# 12V_Power.net
KiCad netlist of a schematic drawn in Altium Designer
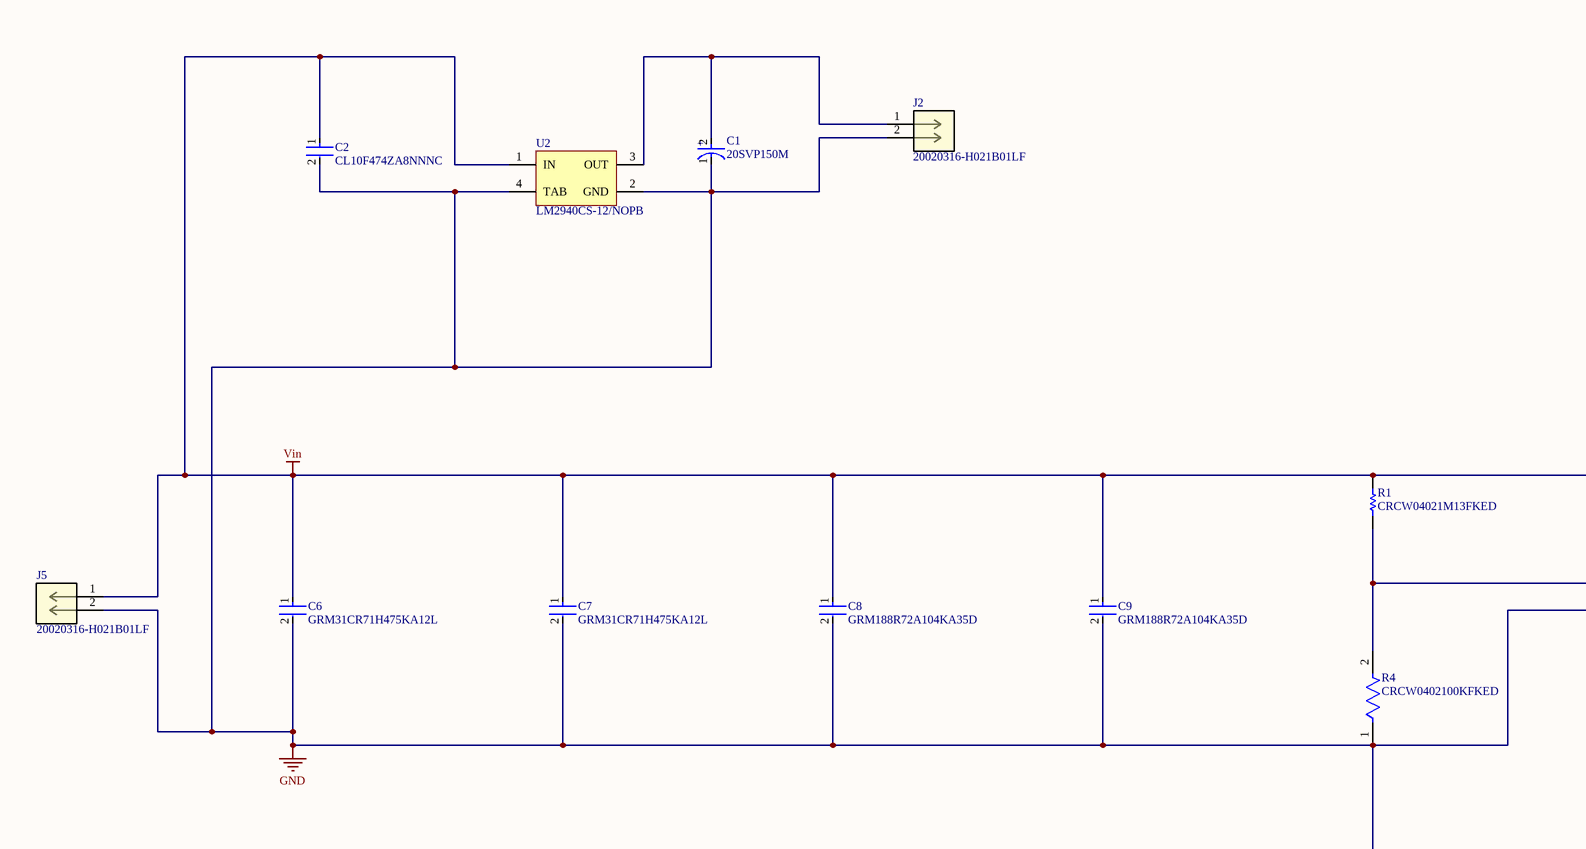
[diagram p0: 12V Power.SchDoc, left]
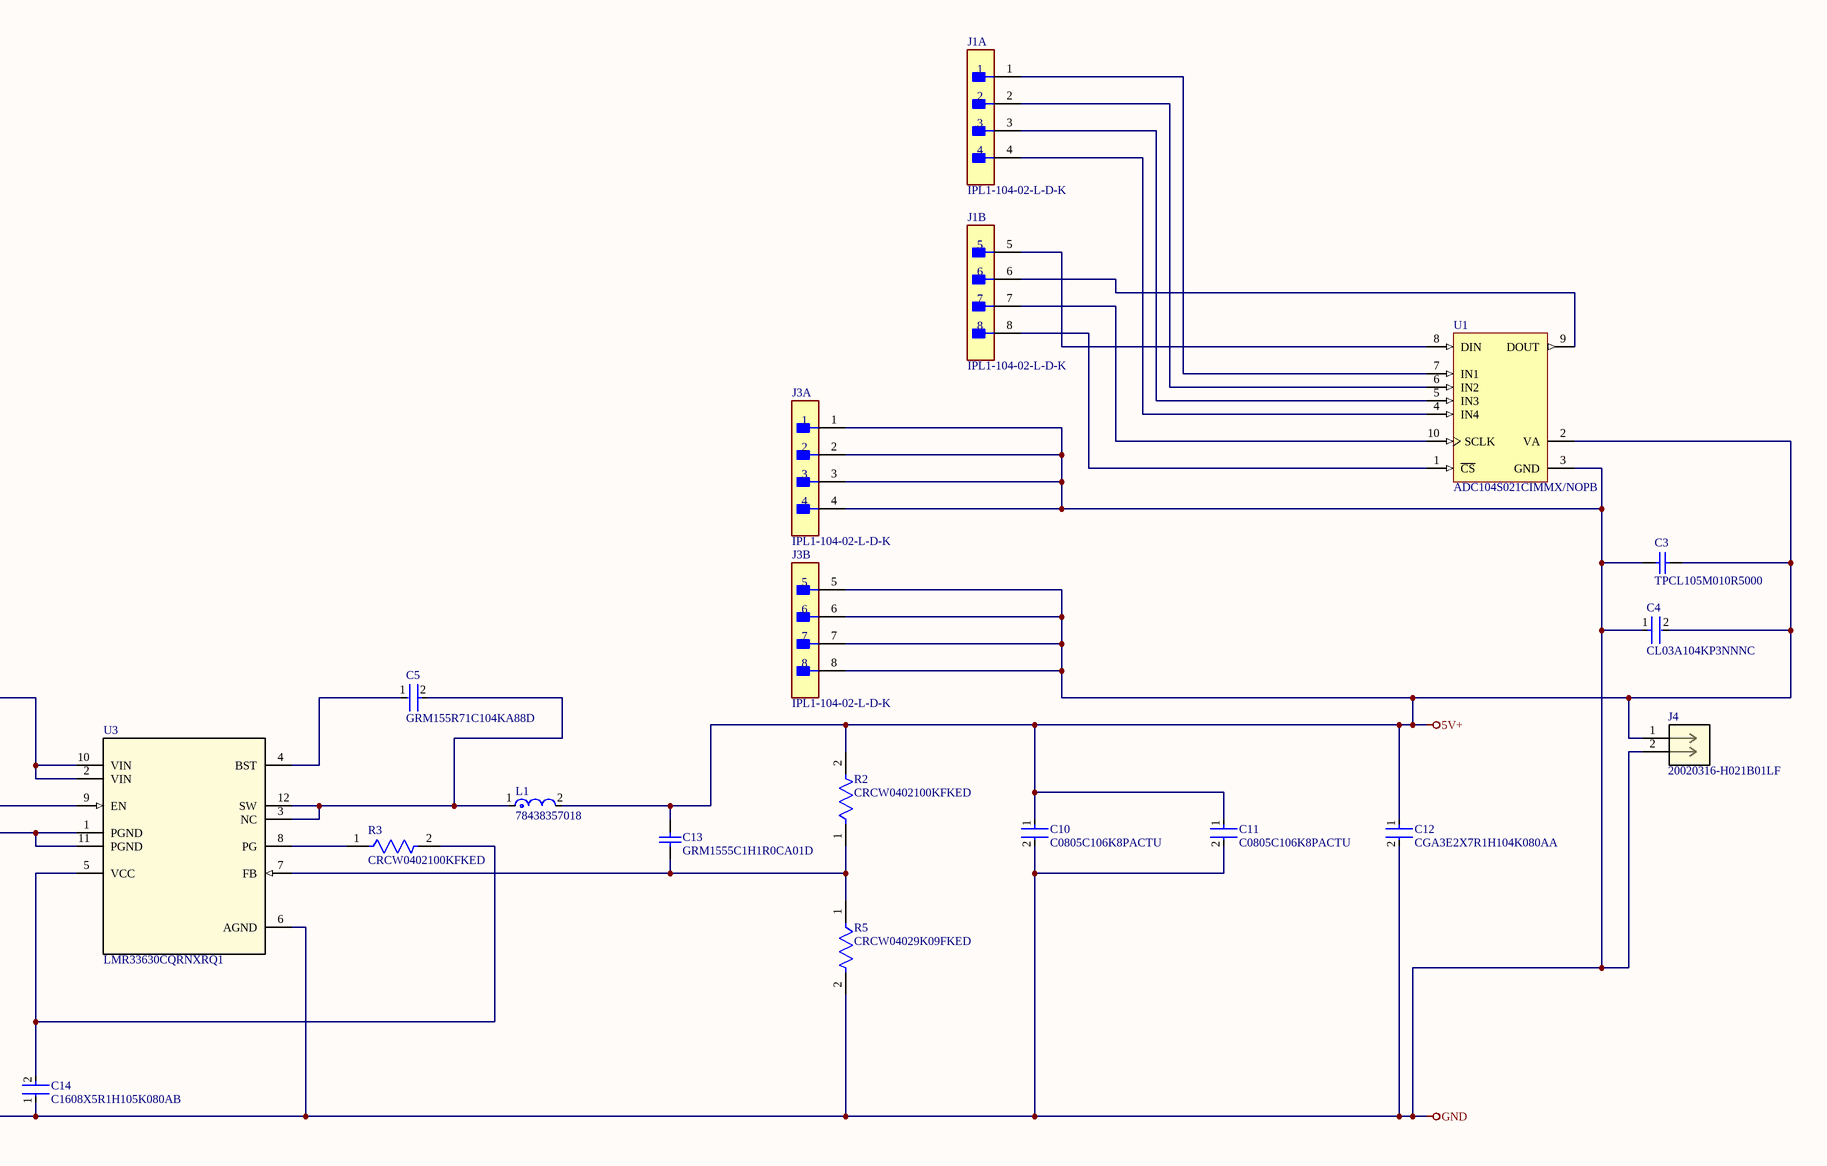
[diagram p1: 12V Power.SchDoc, right]

(export (version "E")
  (design (tool "Eeschema 10.0.6"))
  (components
    (comp (ref "C1")
      (value "20SVP150M")
      (footprint "FP-OS-CON-SMT-F12-MFG")
      (description "Conductive Polymer Aluminum Solid Capacitors (OS-CON) 150uF ±20% 20V RADIAL SMT 10x12.6mm")
      (fields (field (name "TOLERANCE") "20%") (field (name "VOLTAGE") "20V"))
      (libsource (lib "Altium Content Vault") (part "a7907c86e72a156c28511143de7831b"))
    )
    (comp (ref "C2")
      (value "CL10F474ZA8NNNC")
      (footprint "FP-CL10-IPC_C")
      (description "Cap Ceramic 470nF 25V Y5V -20/+80% Pad SMD 0603 +85°C T/R")
      (fields (field (name "TOLERANCE") "80%"))
      (libsource (lib "Altium Content Vault") (part "b4654b650e69147ec39a6b967a45e02"))
    )
    (comp (ref "C3")
      (value "TPCL105M010R5000")
      (footprint "CAPC1609X100X15LL20")
      (fields (field (name "MANUFACTURER") "AVX Interconnect / Elco"))
      (libsource (lib "Altium Content Vault") (part "CAP"))
    )
    (comp (ref "C4")
      (value "CL03A104KP3NNNC")
      (footprint "FP-CL03-IPC_C")
      (description "Cap Ceramic 100nF 10V X5R ±10% Pad SMD 0201 +85°C T/R")
      (fields (field (name "TOLERANCE") "10%"))
      (libsource (lib "Altium Content Vault") (part "b4654b650e69147ec39a6b967a45e02"))
    )
    (comp (ref "C5")
      (value "GRM155R71C104KA88D")
      (footprint "FP-GRM15-MFG")
      (description "CAP CER 0.1UF 16V X7R 0402")
      (fields
        (field (name "TOLERANCE") "10%")
        (field (name "OCTOPART") "https://octopart.com/grm155r71c104ka88d-murata-196880")
      )
      (libsource (lib "Altium Content Vault") (part "236180d848d6139a670b325ea6854c9"))
    )
    (comp (ref "C6")
      (value "GRM31CR71H475KA12L")
      (footprint "FP-GRM31C-0_2-e0_3_0_8-IPC_C")
      (description "Chip Multilayer Ceramic Capacitors for General Purpose, 1206, 4.7uF, X7R, 15%, 10%, 50V")
      (fields (field (name "VOLTAGE") "50V") (field (name "TOLERANCE") "10%"))
      (libsource (lib "Altium Content Vault") (part "02cd4be3c70576c341d710602a673aa"))
    )
    (comp (ref "C7")
      (value "GRM31CR71H475KA12L")
      (footprint "FP-GRM31C-0_2-e0_3_0_8-IPC_C")
      (description "Chip Multilayer Ceramic Capacitors for General Purpose, 1206, 4.7uF, X7R, 15%, 10%, 50V")
      (fields (field (name "VOLTAGE") "50V") (field (name "TOLERANCE") "10%"))
      (libsource (lib "Altium Content Vault") (part "02cd4be3c70576c341d710602a673aa"))
    )
    (comp (ref "C8")
      (value "GRM188R72A104KA35D")
      (footprint "FP-GRM188-0_1-e0_2_0_5-IPC_B")
      (description "Chip Multilayer Ceramic Capacitors for General Purpose, 0603, 0.10uF, X7R, 15%, 10%, 100V")
      (fields (field (name "VOLTAGE") "100V") (field (name "TOLERANCE") "10%"))
      (libsource (lib "Altium Content Vault") (part "11868f565c42a9108669ba33697ecf6"))
    )
    (comp (ref "C9")
      (value "GRM188R72A104KA35D")
      (footprint "FP-GRM188-0_1-e0_2_0_5-IPC_B")
      (description "Chip Multilayer Ceramic Capacitors for General Purpose, 0603, 0.10uF, X7R, 15%, 10%, 100V")
      (fields (field (name "VOLTAGE") "100V") (field (name "TOLERANCE") "10%"))
      (libsource (lib "Altium Content Vault") (part "11868f565c42a9108669ba33697ecf6"))
    )
    (comp (ref "C10")
      (value "C0805C106K8PACTU")
      (footprint "FP-C0805C-DG-MFG")
      (description "CAP CER 10UF 10V X5R 0805")
      (fields (field (name "TOLERANCE") "10%") (field (name "MANUFACTURER") "Kemet"))
      (libsource (lib "Altium Content Vault") (part "11868f565c42a9108669ba33697ecf6"))
    )
    (comp (ref "C11")
      (value "C0805C106K8PACTU")
      (footprint "FP-C0805C-DG-MFG")
      (description "CAP CER 10UF 10V X5R 0805")
      (fields (field (name "TOLERANCE") "10%") (field (name "MANUFACTURER") "Kemet"))
      (libsource (lib "Altium Content Vault") (part "11868f565c42a9108669ba33697ecf6"))
    )
    (comp (ref "C12")
      (value "CGA3E2X7R1H104K080AA")
      (footprint "FP-CGA3E-0_3-0_1-IPC_A")
      (description "Cap Ceramic 100nF 50V X7R 10% Pad SMD 0603 +125°C Automotive T/R")
      (fields (field (name "TOLERANCE") "10%") (field (name "VOLTAGE") "50V"))
      (libsource (lib "Altium Content Vault") (part "b4654b650e69147ec39a6b967a45e02"))
    )
    (comp (ref "C13")
      (value "GRM1555C1H1R0CA01D")
      (footprint "CAPC1005X55X25NL05T10")
      (fields (field (name "MANUFACTURER") "Murata"))
      (libsource (lib "Altium Content Vault") (part "CAP"))
    )
    (comp (ref "C14")
      (value "C1608X5R1H105K080AB")
      (footprint "FP-C1608-080-0_1-IPC_B")
      (description "Multilayer Ceramic Capacitors 1μF ±10% 50V X5R SMD 0603")
      (fields (field (name "VOLTAGE") "50V") (field (name "TOLERANCE") "10%"))
      (libsource (lib "Altium Content Vault") (part "236180d848d6139a670b325ea6854c9"))
    )
    (comp (ref "J1")
      (value "IPL1-104-02-L-D-K")
      (footprint "FP-IPL1-104-02-L-D-K-0")
      (description "4 Position 2 Row .100\" (2.54 mm) pitch connector")
      (libsource (lib "Altium Content Vault") (part "eac520707025fdf6420609226a638dc"))
    )
    (comp (ref "J2")
      (value "20020316-H021B01LF")
      (footprint "CONN_20020316-H021B01LF_AMP")
      (description "No Description Available")
      (fields (field (name "COPYRIGHT") "Copyright (C) 2022 Ultra Librarian. All rights reserved."))
      (libsource (lib "12V Power lib") (part "20020316-H021B01LF"))
    )
    (comp (ref "J3")
      (value "IPL1-104-02-L-D-K")
      (footprint "FP-IPL1-104-02-L-D-K-0")
      (description "4 Position 2 Row .100\" (2.54 mm) pitch connector")
      (libsource (lib "Altium Content Vault") (part "eac520707025fdf6420609226a638dc"))
    )
    (comp (ref "J4")
      (value "20020316-H021B01LF")
      (footprint "CONN_20020316-H021B01LF_AMP")
      (description "No Description Available")
      (fields (field (name "COPYRIGHT") "Copyright (C) 2022 Ultra Librarian. All rights reserved."))
      (libsource (lib "12V Power lib") (part "20020316-H021B01LF"))
    )
    (comp (ref "J5")
      (value "20020316-H021B01LF")
      (footprint "CONN_20020316-H021B01LF_AMP")
      (description "No Description Available")
      (fields (field (name "COPYRIGHT") "Copyright (C) 2022 Ultra Librarian. All rights reserved."))
      (libsource (lib "") (part "20020316-H021B01LF_1"))
    )
    (comp (ref "L1")
      (value "78438357018")
      (footprint "FP-78438357018-MFG")
      (description "FIXED IND 1.8UH 5.8A 21MOHM SMD")
      (fields (field (name "TOLERANCE") "20%"))
      (libsource (lib "Altium Content Vault") (part "4cc4b267dca4c8e51f7102f422741d8"))
    )
    (comp (ref "R1")
      (value "CRCW04021M13FKED")
      (footprint "RESC1005X40X25ML05T05")
      (fields (field (name "MANUFACTURER") "Vishay Dale"))
      (libsource (lib "Altium Content Vault") (part "RES"))
    )
    (comp (ref "R2")
      (value "CRCW0402100KFKED")
      (footprint "FP-CRCW0402-e3-IPC_C")
      (description "RES Thick Film, 100kΩ, 1%, 0.063W, 100ppm/°C, 0402")
      (fields (field (name "TOLERANCE") "1%"))
      (libsource (lib "Altium Content Vault") (part "1029c3af85768c4190bb7ad29bc67b5"))
    )
    (comp (ref "R3")
      (value "CRCW0402100KFKED")
      (footprint "FP-CRCW0402-e3-IPC_C")
      (description "RES Thick Film, 100kΩ, 1%, 0.063W, 100ppm/°C, 0402")
      (fields (field (name "TOLERANCE") "1%"))
      (libsource (lib "Altium Content Vault") (part "1029c3af85768c4190bb7ad29bc67b5"))
    )
    (comp (ref "R4")
      (value "CRCW0402100KFKED")
      (footprint "FP-CRCW0402-e3-IPC_C")
      (description "RES Thick Film, 100kΩ, 1%, 0.063W, 100ppm/°C, 0402")
      (fields (field (name "TOLERANCE") "1%"))
      (libsource (lib "Altium Content Vault") (part "1029c3af85768c4190bb7ad29bc67b5"))
    )
    (comp (ref "R5")
      (value "CRCW04029K09FKED")
      (footprint "FP-CRCW0402-e3-IPC_A")
      (description "RES Thick Film, 9.09kΩ, 1%, 0.063W, 100ppm/°C, 0402")
      (fields (field (name "TOLERANCE") "1%"))
      (libsource (lib "Altium Content Vault") (part "1029c3af85768c4190bb7ad29bc67b5"))
    )
    (comp (ref "U1")
      (value "ADC104S021CIMMX/NOPB")
      (footprint "MUB10A_N")
      (description "4 Channel, 50 kSPS to 200 kSPS, 10-Bit A/D Converter, 10-pin Mini SOIC, Pb-Free")
      (fields (field (name "MANUFACTURER") "National Semiconductor"))
      (libsource (lib "Altium Content Vault") (part "CON-ADC-ADC104S101CIMM"))
    )
    (comp (ref "U2")
      (value "LM2940CS-12/NOPB")
      (footprint "KTT0003B_N")
      (description "1A Low Dropout Regulator, 3-pin TO-263, Pb-Free")
      (fields (field (name "MANUFACTURER") "Texas Instruments"))
      (libsource (lib "Altium Content Vault") (part "PM-REG-LM2940-TO4"))
    )
    (comp (ref "U3")
      (value "LMR33630CQRNXRQ1")
      (footprint "RNX0012B")
      (description "No Description Available")
      (fields (field (name "COPYRIGHT") "Copyright (C) 2022 Ultra Librarian. All rights reserved."))
      (libsource (lib "12V Power lib") (part "LMR33630CQRNXRQ1_1"))
    )
  )
  (nets
    (net (code "1") (name "5V+") (class "Default")
      (node (ref "C10") (pin "1") (pinfunction "1_1") (pintype "passive"))
      (node (ref "C11") (pin "1") (pinfunction "1_1") (pintype "passive"))
      (node (ref "C12") (pin "1") (pinfunction "1_1") (pintype "passive"))
      (node (ref "C13") (pin "2") (pinfunction "2_2") (pintype "passive"))
      (node (ref "C3") (pin "1") (pinfunction "1_1") (pintype "passive"))
      (node (ref "C4") (pin "2") (pinfunction "2_2") (pintype "passive"))
      (node (ref "J3") (pin "5") (pinfunction "5_5") (pintype "passive"))
      (node (ref "J3") (pin "6") (pinfunction "6_6") (pintype "passive"))
      (node (ref "J3") (pin "7") (pinfunction "7_7") (pintype "passive"))
      (node (ref "J3") (pin "8") (pinfunction "8_8") (pintype "passive"))
      (node (ref "J4") (pin "1") (pinfunction "1_1") (pintype "passive"))
      (node (ref "L1") (pin "2") (pinfunction "2_2") (pintype "passive"))
      (node (ref "R2") (pin "2") (pinfunction "2_2") (pintype "passive"))
      (node (ref "U1") (pin "2") (pinfunction "VA_2") (pintype "power_in"))
    )
    (net (code "2") (name "GND") (class "Default")
      (node (ref "C1") (pin "1") (pinfunction "C_1") (pintype "passive"))
      (node (ref "C10") (pin "2") (pinfunction "2_2") (pintype "passive"))
      (node (ref "C11") (pin "2") (pinfunction "2_2") (pintype "passive"))
      (node (ref "C12") (pin "2") (pinfunction "2_2") (pintype "passive"))
      (node (ref "C14") (pin "1") (pinfunction "1_1") (pintype "passive"))
      (node (ref "C2") (pin "2") (pinfunction "2_2") (pintype "passive"))
      (node (ref "C3") (pin "2") (pinfunction "2_2") (pintype "passive"))
      (node (ref "C4") (pin "1") (pinfunction "1_1") (pintype "passive"))
      (node (ref "C6") (pin "2") (pinfunction "2_2") (pintype "passive"))
      (node (ref "C7") (pin "2") (pinfunction "2_2") (pintype "passive"))
      (node (ref "C8") (pin "2") (pinfunction "2_2") (pintype "passive"))
      (node (ref "C9") (pin "2") (pinfunction "2_2") (pintype "passive"))
      (node (ref "J2") (pin "2") (pinfunction "2_2") (pintype "passive"))
      (node (ref "J3") (pin "1") (pinfunction "1_1") (pintype "passive"))
      (node (ref "J3") (pin "2") (pinfunction "2_2") (pintype "passive"))
      (node (ref "J3") (pin "3") (pinfunction "3_3") (pintype "passive"))
      (node (ref "J3") (pin "4") (pinfunction "4_4") (pintype "passive"))
      (node (ref "J4") (pin "2") (pinfunction "2_2") (pintype "passive"))
      (node (ref "J5") (pin "2") (pinfunction "2_2") (pintype "passive"))
      (node (ref "R4") (pin "1") (pinfunction "1_1") (pintype "passive"))
      (node (ref "R5") (pin "2") (pinfunction "2_2") (pintype "passive"))
      (node (ref "U1") (pin "3") (pinfunction "GND_3") (pintype "power_in"))
      (node (ref "U2") (pin "2") (pinfunction "GND_2") (pintype "power_in"))
      (node (ref "U2") (pin "4") (pinfunction "TAB_4") (pintype "power_in"))
      (node (ref "U3") (pin "1") (pinfunction "PGND_1") (pintype "power_in"))
      (node (ref "U3") (pin "11") (pinfunction "PGND_11") (pintype "power_in"))
      (node (ref "U3") (pin "6") (pinfunction "AGND_6") (pintype "power_in"))
    )
    (net (code "3") (name "Net-(C1-A)") (class "Default")
      (node (ref "C1") (pin "2") (pinfunction "A_2") (pintype "passive"))
      (node (ref "J2") (pin "1") (pinfunction "1_1") (pintype "passive"))
      (node (ref "U2") (pin "3") (pinfunction "OUT_3") (pintype "power_in"))
    )
    (net (code "4") (name "Net-(U1-DIN)") (class "Default")
      (node (ref "J1") (pin "5") (pinfunction "5_5") (pintype "passive"))
      (node (ref "U1") (pin "8") (pinfunction "DIN_8") (pintype "input"))
    )
    (net (code "5") (name "Net-(U1-DOUT)") (class "Default")
      (node (ref "J1") (pin "6") (pinfunction "6_6") (pintype "passive"))
      (node (ref "U1") (pin "9") (pinfunction "DOUT_9") (pintype "output"))
    )
    (net (code "6") (name "Net-(U1-IN1)") (class "Default")
      (node (ref "J1") (pin "1") (pinfunction "1_1") (pintype "passive"))
      (node (ref "U1") (pin "7") (pinfunction "IN1_7") (pintype "input"))
    )
    (net (code "7") (name "Net-(U1-IN2)") (class "Default")
      (node (ref "J1") (pin "2") (pinfunction "2_2") (pintype "passive"))
      (node (ref "U1") (pin "6") (pinfunction "IN2_6") (pintype "input"))
    )
    (net (code "8") (name "Net-(U1-IN3)") (class "Default")
      (node (ref "J1") (pin "3") (pinfunction "3_3") (pintype "passive"))
      (node (ref "U1") (pin "5") (pinfunction "IN3_5") (pintype "input"))
    )
    (net (code "9") (name "Net-(U1-IN4)") (class "Default")
      (node (ref "J1") (pin "4") (pinfunction "4_4") (pintype "passive"))
      (node (ref "U1") (pin "4") (pinfunction "IN4_4") (pintype "input"))
    )
    (net (code "10") (name "Net-(U1-SCLK)") (class "Default")
      (node (ref "J1") (pin "7") (pinfunction "7_7") (pintype "passive"))
      (node (ref "U1") (pin "10") (pinfunction "SCLK_10") (pintype "input"))
    )
    (net (code "11") (name "Net-(U1-~{CS})") (class "Default")
      (node (ref "J1") (pin "8") (pinfunction "8_8") (pintype "passive"))
      (node (ref "U1") (pin "1") (pinfunction "~{CS}_1") (pintype "input"))
    )
    (net (code "12") (name "Net-(U3-BST)") (class "Default")
      (node (ref "C5") (pin "1") (pinfunction "1_1") (pintype "passive"))
      (node (ref "U3") (pin "4") (pinfunction "BST_4") (pintype "passive"))
    )
    (net (code "13") (name "Net-(U3-EN)") (class "Default")
      (node (ref "R1") (pin "1") (pinfunction "1_1") (pintype "passive"))
      (node (ref "R4") (pin "2") (pinfunction "2_2") (pintype "passive"))
      (node (ref "U3") (pin "9") (pinfunction "EN_9") (pintype "input"))
    )
    (net (code "14") (name "Net-(U3-FB)") (class "Default")
      (node (ref "C13") (pin "1") (pinfunction "1_1") (pintype "passive"))
      (node (ref "R2") (pin "1") (pinfunction "1_1") (pintype "passive"))
      (node (ref "R5") (pin "1") (pinfunction "1_1") (pintype "passive"))
      (node (ref "U3") (pin "7") (pinfunction "FB_7") (pintype "input"))
    )
    (net (code "15") (name "Net-(U3-NC)") (class "Default")
      (node (ref "C5") (pin "2") (pinfunction "2_2") (pintype "passive"))
      (node (ref "L1") (pin "1") (pinfunction "1_1") (pintype "passive"))
      (node (ref "U3") (pin "12") (pinfunction "SW_12") (pintype "power_in"))
      (node (ref "U3") (pin "3") (pinfunction "NC_3") (pintype "passive"))
    )
    (net (code "16") (name "Net-(U3-PG)") (class "Default")
      (node (ref "R3") (pin "1") (pinfunction "1_1") (pintype "passive"))
      (node (ref "U3") (pin "8") (pinfunction "PG_8") (pintype "open_collector"))
    )
    (net (code "17") (name "Net-(U3-VCC)") (class "Default")
      (node (ref "C14") (pin "2") (pinfunction "2_2") (pintype "passive"))
      (node (ref "R3") (pin "2") (pinfunction "2_2") (pintype "passive"))
      (node (ref "U3") (pin "5") (pinfunction "VCC_5") (pintype "power_in"))
    )
    (net (code "18") (name "Vin") (class "Default")
      (node (ref "C2") (pin "1") (pinfunction "1_1") (pintype "passive"))
      (node (ref "C6") (pin "1") (pinfunction "1_1") (pintype "passive"))
      (node (ref "C7") (pin "1") (pinfunction "1_1") (pintype "passive"))
      (node (ref "C8") (pin "1") (pinfunction "1_1") (pintype "passive"))
      (node (ref "C9") (pin "1") (pinfunction "1_1") (pintype "passive"))
      (node (ref "J5") (pin "1") (pinfunction "1_1") (pintype "passive"))
      (node (ref "R1") (pin "2") (pinfunction "2_2") (pintype "passive"))
      (node (ref "U2") (pin "1") (pinfunction "IN_1") (pintype "power_in"))
      (node (ref "U3") (pin "10") (pinfunction "VIN_10") (pintype "power_in"))
      (node (ref "U3") (pin "2") (pinfunction "VIN_2") (pintype "power_in"))
    )
  )
)
